# Power_Management_System.net
KiCad netlist of a schematic drawn in Altium Designer
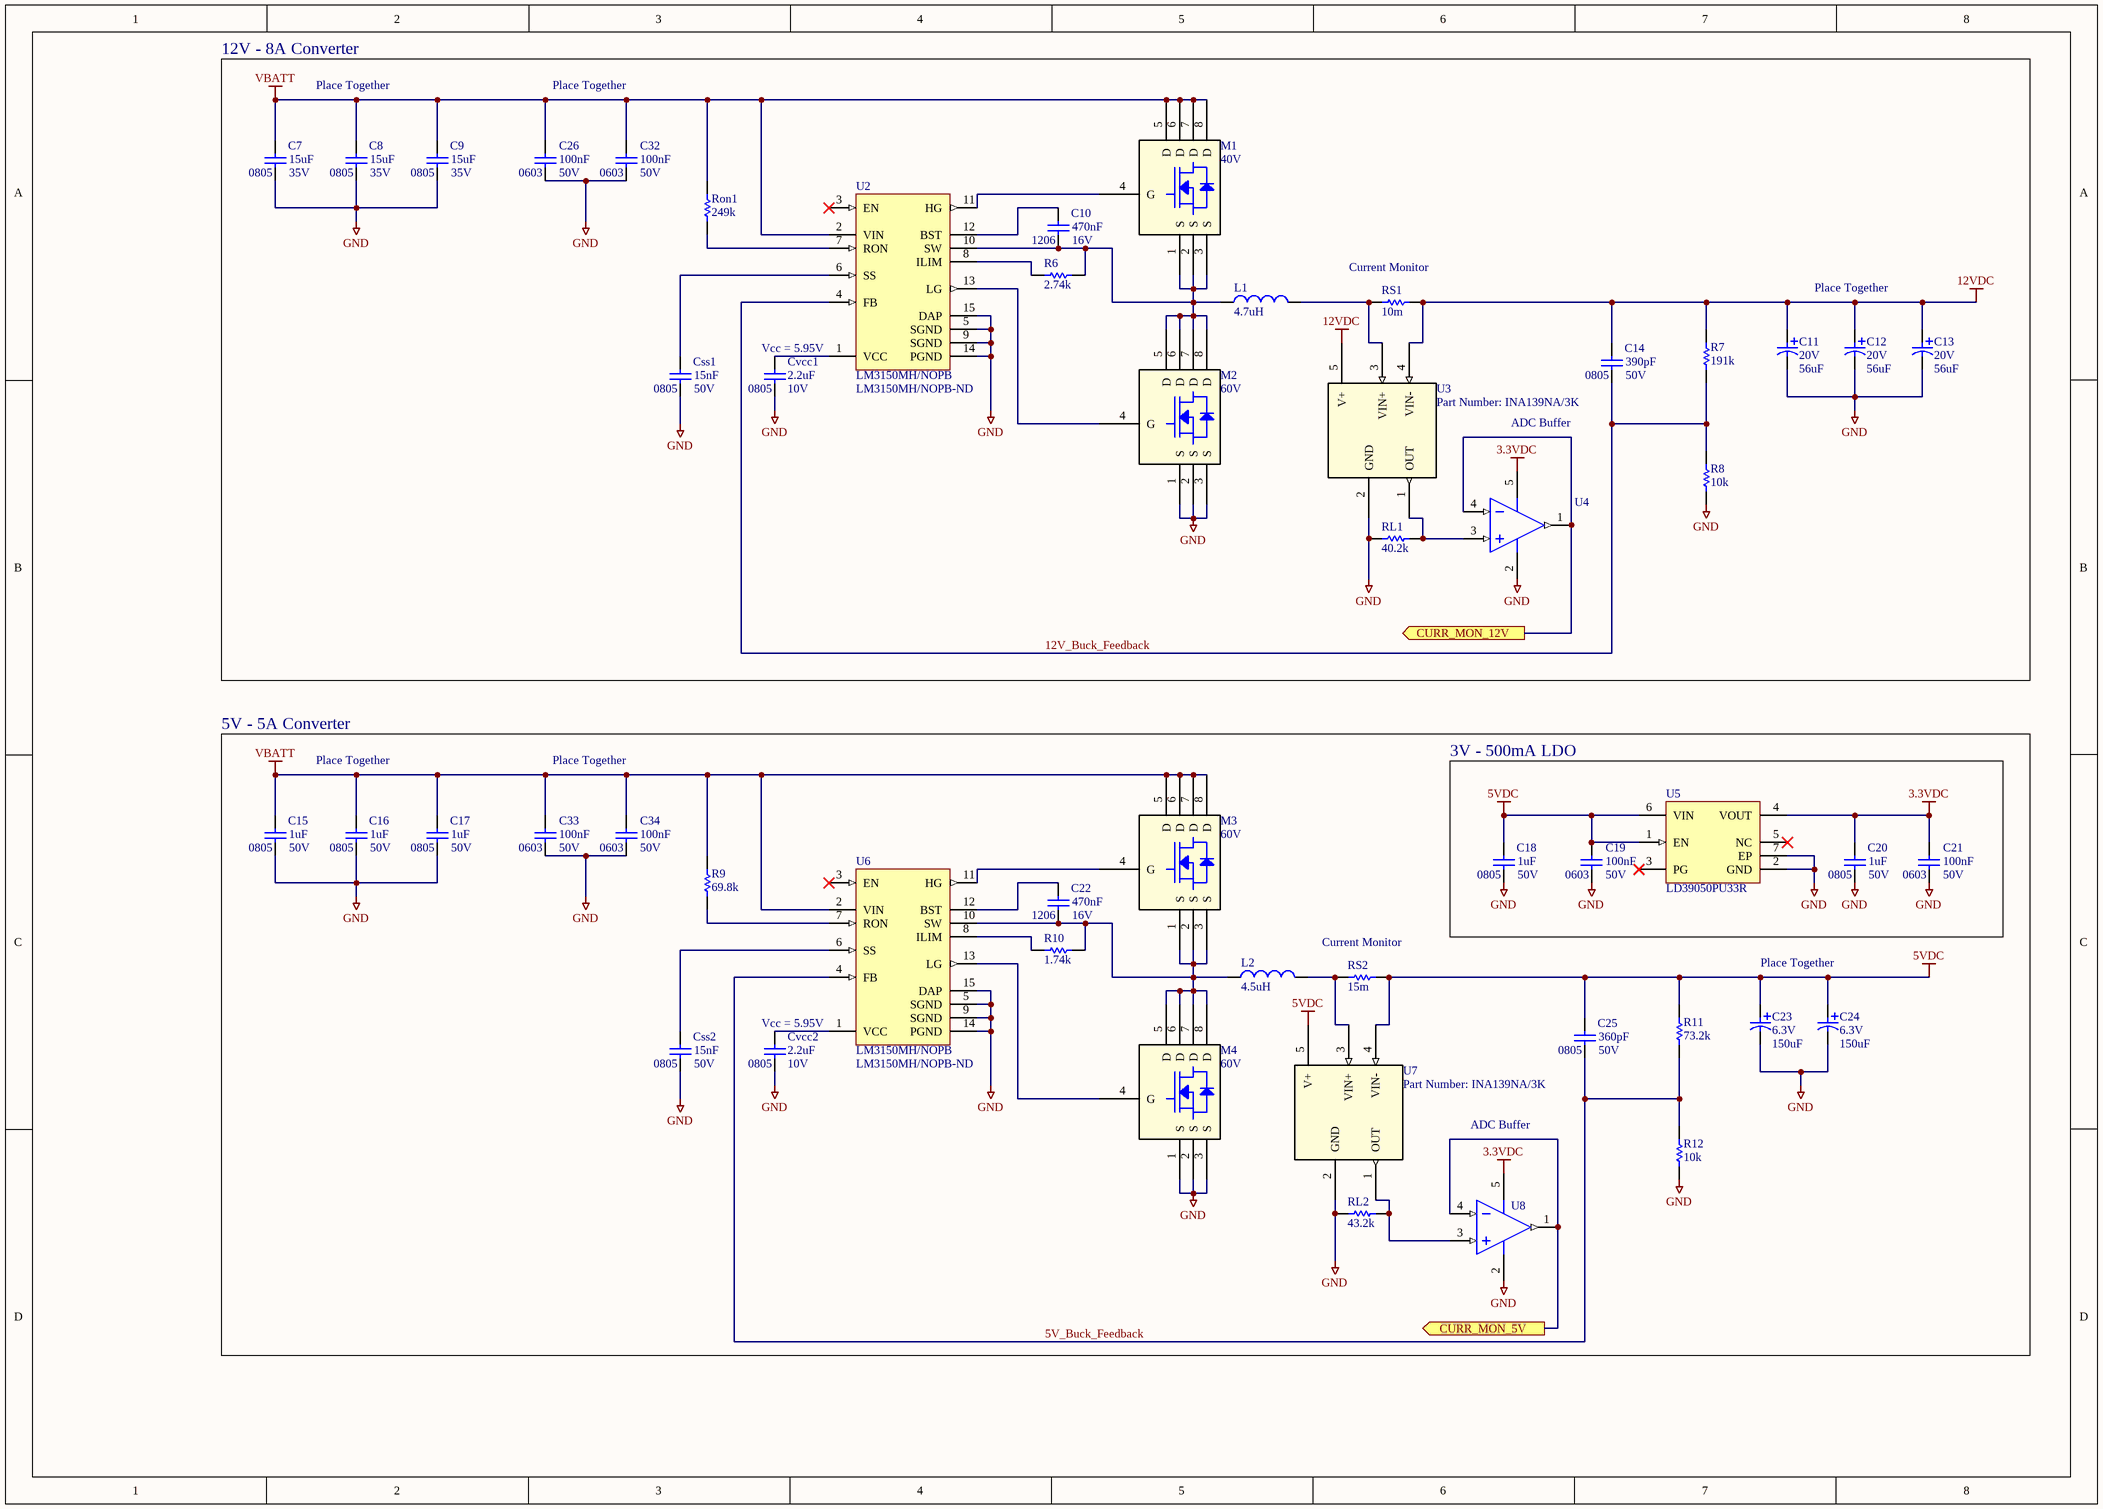
[diagram p0: Power_Management_System.SchDoc]

(export (version "E")
  (design (tool "Eeschema 10.0.6"))
  (components
    (comp (ref "C7")
      (value "C2012X5R1V156M125AC")
      (footprint "CAPC2012N(0805\")")
      (description "CAP CER 15UF 35V X5R 0805")
      (fields
        (field (name "MANUFACTURER") "TDK")
        (field (name "TOLERANCE") "20%")
        (field (name "VOLTAGE RATING") "35V")
        (field (name "CASE/PACKAGE") "0805")
        (field (name "CAPACITANCE") "15uF")
      )
      (libsource (lib "BLDC_Gimbal_Prototype_Lib") (part "C2012X5R1V156M125AC"))
    )
    (comp (ref "C8")
      (value "C2012X5R1V156M125AC")
      (footprint "CAPC2012N(0805\")")
      (description "CAP CER 15UF 35V X5R 0805")
      (fields
        (field (name "MANUFACTURER") "TDK")
        (field (name "TOLERANCE") "20%")
        (field (name "VOLTAGE RATING") "35V")
        (field (name "CASE/PACKAGE") "0805")
        (field (name "CAPACITANCE") "15uF")
      )
      (libsource (lib "BLDC_Gimbal_Prototype_Lib") (part "C2012X5R1V156M125AC"))
    )
    (comp (ref "C9")
      (value "C2012X5R1V156M125AC")
      (footprint "CAPC2012N(0805\")")
      (description "CAP CER 15UF 35V X5R 0805")
      (fields
        (field (name "MANUFACTURER") "TDK")
        (field (name "TOLERANCE") "20%")
        (field (name "VOLTAGE RATING") "35V")
        (field (name "CASE/PACKAGE") "0805")
        (field (name "CAPACITANCE") "15uF")
      )
      (libsource (lib "BLDC_Gimbal_Prototype_Lib") (part "C2012X5R1V156M125AC"))
    )
    (comp (ref "C10")
      (value "ECP-U1C474MA5")
      (footprint "CAPC3216N(1206\")")
      (description "CAP FILM 0.47UF 20% 16VDC 1206")
      (fields
        (field (name "MANUFACTURER") "Panasonic")
        (field (name "TOLERANCE") "20%")
        (field (name "VOLTAGE RATING") "16V")
        (field (name "CASE CODE (IMPERIAL)") "1206")
        (field (name "CAPACITANCE") "470nF")
      )
      (libsource (lib "BLDC_Gimbal_Prototype_Lib") (part "ECP-U1C474MA5"))
    )
    (comp (ref "C11")
      (value "20SVPF56MX")
      (footprint "PCAP_SVP_B6-M")
      (description "CAP ALUM POLY 56UF 20% 20V SMD")
      (fields
        (field (name "MANUFACTURER") "Panasonic")
        (field (name "TOLERANCE") "20%")
        (field (name "VOLTAGE") "20V")
        (field (name "CAPACITANCE") "56uF")
      )
      (libsource (lib "BLDC_Gimbal_Lib") (part "20SVPF56MX"))
    )
    (comp (ref "C12")
      (value "20SVPF56MX")
      (footprint "PCAP_SVP_B6-M")
      (description "CAP ALUM POLY 56UF 20% 20V SMD")
      (fields
        (field (name "MANUFACTURER") "Panasonic")
        (field (name "TOLERANCE") "20%")
        (field (name "VOLTAGE") "20V")
        (field (name "CAPACITANCE") "56uF")
      )
      (libsource (lib "BLDC_Gimbal_Lib") (part "20SVPF56MX"))
    )
    (comp (ref "C13")
      (value "20SVPF56MX")
      (footprint "PCAP_SVP_B6-M")
      (description "CAP ALUM POLY 56UF 20% 20V SMD")
      (fields
        (field (name "MANUFACTURER") "Panasonic")
        (field (name "TOLERANCE") "20%")
        (field (name "VOLTAGE") "20V")
        (field (name "CAPACITANCE") "56uF")
      )
      (libsource (lib "BLDC_Gimbal_Lib") (part "20SVPF56MX"))
    )
    (comp (ref "C14")
      (value "C0805C391J5GACTU")
      (footprint "CAPC2012N(0805\")")
      (description "CAP CER 390PF 50V C0G/NP0 0805")
      (fields
        (field (name "MANUFACTURER") "KEMET")
        (field (name "TOLERANCE") "5%")
        (field (name "VOLTAGE") "50V")
        (field (name "CASE/PACKAGE") "0805")
        (field (name "CAPACITANCE") "390pF")
      )
      (libsource (lib "BLDC_Gimbal_Prototype_Lib") (part "C0805C391J5GACTU"))
    )
    (comp (ref "C15")
      (value "CL21A105KBCLNNC")
      (footprint "CAPC2012N(0805\")")
      (description "CAP CER 1uF 50V X5R 10% SMD 0805 85C Cardboard T/R")
      (fields
        (field (name "MANUFACTURER") "Samsung")
        (field (name "TOLERANCE") "10%")
        (field (name "VOLTAGE RATING") "50V")
        (field (name "CASE/PACKAGE") "0805")
        (field (name "CAPACITANCE") "1uF")
      )
      (libsource (lib "BLDC_Gimbal_Prototype_Lib") (part "CL21A105KBCLNNC"))
    )
    (comp (ref "C16")
      (value "CL21A105KBCLNNC")
      (footprint "CAPC2012N(0805\")")
      (description "CAP CER 1uF 50V X5R 10% SMD 0805 85C Cardboard T/R")
      (fields
        (field (name "MANUFACTURER") "Samsung")
        (field (name "TOLERANCE") "10%")
        (field (name "VOLTAGE RATING") "50V")
        (field (name "CASE/PACKAGE") "0805")
        (field (name "CAPACITANCE") "1uF")
      )
      (libsource (lib "BLDC_Gimbal_Prototype_Lib") (part "CL21A105KBCLNNC"))
    )
    (comp (ref "C17")
      (value "CL21A105KBCLNNC")
      (footprint "CAPC2012N(0805\")")
      (description "CAP CER 1uF 50V X5R 10% SMD 0805 85C Cardboard T/R")
      (fields
        (field (name "MANUFACTURER") "Samsung")
        (field (name "TOLERANCE") "10%")
        (field (name "VOLTAGE RATING") "50V")
        (field (name "CASE/PACKAGE") "0805")
        (field (name "CAPACITANCE") "1uF")
      )
      (libsource (lib "BLDC_Gimbal_Prototype_Lib") (part "CL21A105KBCLNNC"))
    )
    (comp (ref "C18")
      (value "CL21A105KBCLNNC")
      (footprint "CAPC2012N(0805\")")
      (description "CAP CER 1uF 50V X5R 10% SMD 0805 85C Cardboard T/R")
      (fields
        (field (name "MANUFACTURER") "Samsung")
        (field (name "TOLERANCE") "10%")
        (field (name "VOLTAGE RATING") "50V")
        (field (name "CASE/PACKAGE") "0805")
        (field (name "CAPACITANCE") "1uF")
      )
      (libsource (lib "BLDC_Gimbal_Lib") (part "CL21A105KBCLNNC"))
    )
    (comp (ref "C19")
      (value "100nF")
      (footprint "CAPC1608N(0603\")")
      (description "CAP CER 0.1UF 50V X7R 0603")
      (fields
        (field (name "MANUFACTURER") "Samsung")
        (field (name "MANUFACTURER PART NUMBER") "CL10B104KB8SFNC")
        (field (name "CASE CODE (IMPERIAL)") "0603")
        (field (name "VOLTAGE RATING") "50V")
      )
      (libsource (lib "BLDC_Gimbal_Lib") (part "CL10B104KB8SFNC"))
    )
    (comp (ref "C20")
      (value "CL21A105KBCLNNC")
      (footprint "CAPC2012N(0805\")")
      (description "CAP CER 1uF 50V X5R 10% SMD 0805 85C Cardboard T/R")
      (fields
        (field (name "MANUFACTURER") "Samsung")
        (field (name "TOLERANCE") "10%")
        (field (name "VOLTAGE RATING") "50V")
        (field (name "CASE/PACKAGE") "0805")
        (field (name "CAPACITANCE") "1uF")
      )
      (libsource (lib "BLDC_Gimbal_Lib") (part "CL21A105KBCLNNC"))
    )
    (comp (ref "C21")
      (value "100nF")
      (footprint "CAPC1608N(0603\")")
      (description "CAP CER 0.1UF 50V X7R 0603")
      (fields
        (field (name "MANUFACTURER") "Samsung")
        (field (name "MANUFACTURER PART NUMBER") "CL10B104KB8SFNC")
        (field (name "CASE CODE (IMPERIAL)") "0603")
        (field (name "VOLTAGE RATING") "50V")
      )
      (libsource (lib "BLDC_Gimbal_Lib") (part "CL10B104KB8SFNC"))
    )
    (comp (ref "C22")
      (value "ECP-U1C474MA5")
      (footprint "CAPC3216N(1206\")")
      (description "CAP FILM 0.47UF 20% 16VDC 1206")
      (fields
        (field (name "MANUFACTURER") "Panasonic")
        (field (name "TOLERANCE") "20%")
        (field (name "VOLTAGE RATING") "16V")
        (field (name "CASE CODE (IMPERIAL)") "1206")
        (field (name "CAPACITANCE") "470nF")
      )
      (libsource (lib "BLDC_Gimbal_Prototype_Lib") (part "ECP-U1C474MA5"))
    )
    (comp (ref "C23")
      (value "6SVPE150M")
      (footprint "PCAP_SVP_B6-M")
      (description "CAP ALUM POLY 150UF 20% 6.3V SMD")
      (fields
        (field (name "MANUFACTURER") "Panasonic")
        (field (name "TOLERANCE") "20%")
        (field (name "VOLTAGE") "6.3V")
        (field (name "CAPACITANCE") "150uF")
      )
      (libsource (lib "BLDC_Gimbal_Lib") (part "6SVPE150M"))
    )
    (comp (ref "C24")
      (value "6SVPE150M")
      (footprint "PCAP_SVP_B6-M")
      (description "CAP ALUM POLY 150UF 20% 6.3V SMD")
      (fields
        (field (name "MANUFACTURER") "Panasonic")
        (field (name "TOLERANCE") "20%")
        (field (name "VOLTAGE") "6.3V")
        (field (name "CAPACITANCE") "150uF")
      )
      (libsource (lib "BLDC_Gimbal_Lib") (part "6SVPE150M"))
    )
    (comp (ref "C25")
      (value "CL21C361JBANNNC")
      (footprint "CAPC2012N(0805\")")
      (description "CAP CER 360pF 50V C0G 5% SMD 0805 125C Paper T/R")
      (fields
        (field (name "MANUFACTURER") "Samsung")
        (field (name "TOLERANCE") "5%")
        (field (name "VOLTAGE RATING") "50V")
        (field (name "CASE/PACKAGE") "0805")
        (field (name "CAPACITANCE") "360pF")
      )
      (libsource (lib "BLDC_Gimbal_Prototype_Lib") (part "CL21C361JBANNNC"))
    )
    (comp (ref "C26")
      (value "100nF")
      (footprint "CAPC1608N(0603\")")
      (description "CAP CER 0.1UF 50V X7R 0603")
      (fields
        (field (name "MANUFACTURER") "Samsung")
        (field (name "MANUFACTURER PART NUMBER") "CL10B104KB8SFNC")
        (field (name "CASE CODE (IMPERIAL)") "0603")
        (field (name "VOLTAGE RATING") "50V")
      )
      (libsource (lib "BLDC_Gimbal_Lib") (part "CL10B104KB8SFNC"))
    )
    (comp (ref "C32")
      (value "100nF")
      (footprint "CAPC1608N(0603\")")
      (description "CAP CER 0.1UF 50V X7R 0603")
      (fields
        (field (name "MANUFACTURER") "Samsung")
        (field (name "MANUFACTURER PART NUMBER") "CL10B104KB8SFNC")
        (field (name "CASE CODE (IMPERIAL)") "0603")
        (field (name "VOLTAGE RATING") "50V")
      )
      (libsource (lib "BLDC_Gimbal_Lib") (part "CL10B104KB8SFNC"))
    )
    (comp (ref "C33")
      (value "100nF")
      (footprint "CAPC1608N(0603\")")
      (description "CAP CER 0.1UF 50V X7R 0603")
      (fields
        (field (name "MANUFACTURER") "Samsung")
        (field (name "MANUFACTURER PART NUMBER") "CL10B104KB8SFNC")
        (field (name "CASE CODE (IMPERIAL)") "0603")
        (field (name "VOLTAGE RATING") "50V")
      )
      (libsource (lib "BLDC_Gimbal_Lib") (part "CL10B104KB8SFNC"))
    )
    (comp (ref "C34")
      (value "100nF")
      (footprint "CAPC1608N(0603\")")
      (description "CAP CER 0.1UF 50V X7R 0603")
      (fields
        (field (name "MANUFACTURER") "Samsung")
        (field (name "MANUFACTURER PART NUMBER") "CL10B104KB8SFNC")
        (field (name "CASE CODE (IMPERIAL)") "0603")
        (field (name "VOLTAGE RATING") "50V")
      )
      (libsource (lib "BLDC_Gimbal_Lib") (part "CL10B104KB8SFNC"))
    )
    (comp (ref "Css1")
      (value "CGA4F2C0G1H153J085AA")
      (footprint "CAPC2012N(0805\")")
      (description "CAP, 0.015µF, 50V, 5%, C0G/NP0, 0805")
      (fields
        (field (name "MANUFACTURER") "TDK")
        (field (name "TOLERANCE") "5%")
        (field (name "VOLTAGE RATING") "50V")
        (field (name "CASE/PACKAGE") "0805")
        (field (name "CAPACITANCE") "15nF")
      )
      (libsource (lib "BLDC_Gimbal_Prototype_Lib") (part "CGA4F2C0G1H153J085AA"))
    )
    (comp (ref "Css2")
      (value "CGA4F2C0G1H153J085AA")
      (footprint "CAPC2012N(0805\")")
      (description "CAP, 0.015µF, 50V, 5%, C0G/NP0, 0805")
      (fields
        (field (name "MANUFACTURER") "TDK")
        (field (name "TOLERANCE") "5%")
        (field (name "VOLTAGE RATING") "50V")
        (field (name "CASE/PACKAGE") "0805")
        (field (name "CAPACITANCE") "15nF")
      )
      (libsource (lib "BLDC_Gimbal_Prototype_Lib") (part "CGA4F2C0G1H153J085AA"))
    )
    (comp (ref "Cvcc1")
      (value "LMK212B7225KG-T")
      (footprint "CAPC2012N(0805\")")
      (description "CAP CER 2.2UF 10V X7R 0805")
      (fields
        (field (name "MANUFACTURER") "Taiyo Yuden")
        (field (name "TOLERANCE") "10%")
        (field (name "CAPACITANCE") "2.2uF")
        (field (name "VOLTAGE RATING") "10V")
        (field (name "CASE/PACKAGE") "0805")
      )
      (libsource (lib "BLDC_Gimbal_Prototype_Lib") (part "LMK212B7225KG-T"))
    )
    (comp (ref "Cvcc2")
      (value "LMK212B7225KG-T")
      (footprint "CAPC2012N(0805\")")
      (description "CAP CER 2.2UF 10V X7R 0805")
      (fields
        (field (name "MANUFACTURER") "Taiyo Yuden")
        (field (name "TOLERANCE") "10%")
        (field (name "CAPACITANCE") "2.2uF")
        (field (name "VOLTAGE RATING") "10V")
        (field (name "CASE/PACKAGE") "0805")
      )
      (libsource (lib "BLDC_Gimbal_Prototype_Lib") (part "LMK212B7225KG-T"))
    )
    (comp (ref "L1")
      (value "SRP1270-4R7M")
      (footprint "IND_BOURNS_SRP01_large")
      (description "FIXED IND 4.7uH 20% SMD 1270")
      (fields
        (field (name "MANUFACTURER") "Bourns")
        (field (name "TOLERANCE") "20%")
        (field (name "INDUCTANCE") "4.7uH")
      )
      (libsource (lib "BLDC_Gimbal_Lib") (part "SRP1270-4R7M"))
    )
    (comp (ref "L2")
      (value "SRR1208-4R5ML")
      (footprint "IND_BOURNS_SRR12")
      (description "FIXED IND 4.5UH 6.5A 14 MOHM SMD")
      (fields
        (field (name "MANUFACTURER") "Bourns")
        (field (name "TOLERANCE") "20%")
        (field (name "INDUCTANCE") "4.5uH")
      )
      (libsource (lib "BLDC_Gimbal_Lib") (part "SRR1208-4R5ML"))
    )
    (comp (ref "M1")
      (value "CSD18504Q5A")
      (footprint "DQJ8")
      (description "MOSFET N-CH 40V 8SON")
      (fields
        (field (name "MANUFACTURER") "Texas Instruments")
        (field (name "DRAIN TO SOURCE VOLTAGE (VDSS)") "40V")
      )
      (libsource (lib "BLDC_Gimbal_Prototype_Lib") (part "CSD18504Q5A"))
    )
    (comp (ref "M2")
      (value "CSD18537NQ5A")
      (footprint "DQJ8")
      (description "MOSFET N-CH 60V 50A 8-Pin VSON-FET EP T/R")
      (fields
        (field (name "MANUFACTURER") "Texas Instruments")
        (field (name "DRAIN TO SOURCE VOLTAGE (VDSS)") "60V")
      )
      (libsource (lib "BLDC_Gimbal_Prototype_Lib") (part "CSD18537NQ5A"))
    )
    (comp (ref "M3")
      (value "CSD18537NQ5A")
      (footprint "DQJ8")
      (description "MOSFET N-CH 60V 50A 8-Pin VSON-FET EP T/R")
      (fields
        (field (name "MANUFACTURER") "Texas Instruments")
        (field (name "DRAIN TO SOURCE VOLTAGE (VDSS)") "60V")
      )
      (libsource (lib "BLDC_Gimbal_Prototype_Lib") (part "CSD18537NQ5A"))
    )
    (comp (ref "M4")
      (value "CSD18537NQ5A")
      (footprint "DQJ8")
      (description "MOSFET N-CH 60V 50A 8-Pin VSON-FET EP T/R")
      (fields
        (field (name "MANUFACTURER") "Texas Instruments")
        (field (name "DRAIN TO SOURCE VOLTAGE (VDSS)") "60V")
      )
      (libsource (lib "BLDC_Gimbal_Prototype_Lib") (part "CSD18537NQ5A"))
    )
    (comp (ref "R6")
      (value "ERJ-6ENF2741V")
      (footprint "RESC2012N(0805\")")
      (description "RES SMD 2.74K OHM 1% 1/8W 0805")
      (fields
        (field (name "MANUFACTURER") "Panasonic")
        (field (name "TOLERANCE") "1%")
        (field (name "RESISTANCE") "2.74k")
      )
      (libsource (lib "BLDC_Gimbal_Prototype_Lib") (part "ERJ-6ENF2741V"))
    )
    (comp (ref "R7")
      (value "ERJ-6ENF1913V")
      (footprint "RESC2012N(0805\")")
      (description "RES SMD 191K OHM 1% 1/8W 0805")
      (fields
        (field (name "MANUFACTURER") "Panasonic")
        (field (name "TOLERANCE") "1%")
        (field (name "RESISTANCE") "191k")
      )
      (libsource (lib "BLDC_Gimbal_Prototype_Lib") (part "ERJ-6ENF1913V"))
    )
    (comp (ref "R8")
      (value "CRCW080510K0FKEA")
      (footprint "RESC2012N(0805\")")
      (description "RES SMD 10K OHM 1% 1/8W 0805")
      (fields
        (field (name "MANUFACTURER") "Vishay")
        (field (name "TOLERANCE") "1%")
        (field (name "RESISTANCE") "10k")
      )
      (libsource (lib "BLDC_Gimbal_Prototype_Lib") (part "CRCW080510K0FKEA"))
    )
    (comp (ref "R9")
      (value "ERJ-6ENF6982V")
      (footprint "RESC2012N(0805\")")
      (description "RES SMD 69.8K OHM 1% 1/8W 0805")
      (fields
        (field (name "MANUFACTURER") "Panasonic")
        (field (name "TOLERANCE") "1%")
        (field (name "RESISTANCE") "69.8k")
      )
      (libsource (lib "BLDC_Gimbal_Prototype_Lib") (part "ERJ-6ENF6982V"))
    )
    (comp (ref "R10")
      (value "ERJ6ENF1741V")
      (footprint "RESC2012N(0805\")")
      (description "RES SMD 1.74K OHM 1% 1/8W 0805")
      (fields
        (field (name "MANUFACTURER") "Panasonic")
        (field (name "TOLERANCE") "1%")
        (field (name "RESISTANCE") "1.74k")
      )
      (libsource (lib "BLDC_Gimbal_Prototype_Lib") (part "ERJ6ENF1741V"))
    )
    (comp (ref "R11")
      (value "ERJ-6ENF7322V")
      (footprint "RESC2012N(0805\")")
      (description "RES SMD 73.2K OHM 1% 1/8W 0805")
      (fields
        (field (name "MANUFACTURER") "Panasonic")
        (field (name "TOLERANCE") "1%")
        (field (name "RESISTANCE") "73.2k")
      )
      (libsource (lib "BLDC_Gimbal_Prototype_Lib") (part "ERJ-6ENF7322V"))
    )
    (comp (ref "R12")
      (value "CRCW080510K0FKEA")
      (footprint "RESC2012N(0805\")")
      (description "RES SMD 10K OHM 1% 1/8W 0805")
      (fields
        (field (name "MANUFACTURER") "Vishay")
        (field (name "TOLERANCE") "1%")
        (field (name "RESISTANCE") "10k")
      )
      (libsource (lib "BLDC_Gimbal_Prototype_Lib") (part "CRCW080510K0FKEA"))
    )
    (comp (ref "RL1")
      (value "ERA3AEB4022V")
      (footprint "RESC1608N(0603\")")
      (description "RES SMD 40.2K OHM 0.1% 1/10W 0603")
      (fields
        (field (name "MANUFACTURER") "Panasonic")
        (field (name "TOLERANCE") "0.1%")
        (field (name "RESISTANCE") "40.2k")
      )
      (libsource (lib "BLDC_Gimbal_Prototype_Lib") (part "ERA3AEB4022V"))
    )
    (comp (ref "RL2")
      (value "ERA3AEB4322V")
      (footprint "RESC1608N(0603\")")
      (description "RES SMD 43.2K OHM 0.1% 1/10W 0603")
      (fields
        (field (name "MANUFACTURER") "Panasonic")
        (field (name "TOLERANCE") "0.1%")
        (field (name "RESISTANCE") "43.2k")
      )
      (libsource (lib "BLDC_Gimbal_Prototype_Lib") (part "ERA3AEB4322V"))
    )
    (comp (ref "Ron1")
      (value "CRCW0805249KFKEA")
      (footprint "RESC2012N(0805\")")
      (description "RES SMD 249K OHM 1% 1/8W 0805")
      (fields
        (field (name "MANUFACTURER") "Vishay")
        (field (name "TOLERANCE") "1%")
        (field (name "RESISTANCE") "249k")
      )
      (libsource (lib "BLDC_Gimbal_Prototype_Lib") (part "CRCW0805249KFKEA"))
    )
    (comp (ref "RS1")
      (value "CRA2512-FZ-R010ELF")
      (footprint "RESC6332N(2512\")")
      (description "RES SMD 10 MOHM, 2512 [6432 Metric], 3 W,  1%, CR Series")
      (fields
        (field (name "MANUFACTURER") "Bourns")
        (field (name "TOLERANCE") "1%")
        (field (name "RESISTANCE") "10m")
      )
      (libsource (lib "BLDC_Gimbal_Prototype_Lib") (part "CRA2512-FZ-R010ELF"))
    )
    (comp (ref "RS2")
      (value "CRA2512-FZ-R015ELF")
      (footprint "RESC6332N(2512\")")
      (description "RES SMD 15 MOHM 1% 3W 2512")
      (fields
        (field (name "MANUFACTURER") "Bourns")
        (field (name "TOLERANCE") "1%")
        (field (name "RESISTANCE") "15m")
      )
      (libsource (lib "BLDC_Gimbal_Prototype_Lib") (part "CRA2512-FZ-R015ELF"))
    )
    (comp (ref "U2")
      (value "LM3150MH/NOPB")
      (footprint "PWP0014A_M")
      (description "LM3150 - DC DC Cntrlr Single-OUT Step Down 6V to 42V Input 14-Pin HTSSOP EP Tube")
      (fields
        (field (name "MANUFACTURER") "TI National Semiconductor")
        (field (name "SUPPLIER PART NUMBER 1") "LM3150MH/NOPB-ND")
      )
      (libsource (lib "BLDC_Gimbal_Lib") (part "LM3150MH/NOPB"))
    )
    (comp (ref "U3")
      (value "Part Number: INA139NA/3K")
      (footprint "DBV5-M")
      (description "No Description Available")
      (fields
        (field (name "MANUFACTURER") "Texas Instruments")
        (field (name "MANUFACTURER_PART_NUMBER") "INA139NA/3K")
        (field (name "COPYRIGHT") "Copyright (C) 2018 Accelerated Designs. All rights reserved")
      )
      (libsource (lib "BLDC_Gimbal_Prototype_Lib") (part "INA139NA/3K"))
    )
    (comp (ref "U4")
      (value "OPA340NA/3K")
      (footprint "DBV0005A_M")
      (fields (field (name "MANUFACTURER") "Texas Instruments"))
      (libsource (lib "BLDC_Gimbal_Prototype_Lib") (part "CMP-0272-00929-3"))
    )
    (comp (ref "U5")
      (value "LD39050PU33R")
      (footprint "LDO3_3-DFN6D_M")
      (libsource (lib "BLDC_Gimbal_Lib") (part "LD39050PU33R"))
    )
    (comp (ref "U6")
      (value "LM3150MH/NOPB")
      (footprint "PWP0014A_M")
      (description "LM3150 - DC DC Cntrlr Single-OUT Step Down 6V to 42V Input 14-Pin HTSSOP EP Tube")
      (fields
        (field (name "MANUFACTURER") "TI National Semiconductor")
        (field (name "SUPPLIER PART NUMBER 1") "LM3150MH/NOPB-ND")
      )
      (libsource (lib "BLDC_Gimbal_Lib") (part "LM3150MH/NOPB"))
    )
    (comp (ref "U7")
      (value "Part Number: INA139NA/3K")
      (footprint "DBV5-M")
      (description "No Description Available")
      (fields
        (field (name "MANUFACTURER") "Texas Instruments")
        (field (name "MANUFACTURER_PART_NUMBER") "INA139NA/3K")
        (field (name "COPYRIGHT") "Copyright (C) 2018 Accelerated Designs. All rights reserved")
      )
      (libsource (lib "BLDC_Gimbal_Prototype_Lib") (part "INA139NA/3K"))
    )
    (comp (ref "U8")
      (value "OPA340NA/3K")
      (footprint "DBV0005A_M")
      (fields (field (name "MANUFACTURER") "Texas Instruments"))
      (libsource (lib "BLDC_Gimbal_Prototype_Lib") (part "CMP-0272-00929-3"))
    )
  )
  (nets
    (net (code "1") (name "/5V_Buck_Feedback") (class "Default")
      (node (ref "C25") (pin "1") (pinfunction "1_1") (pintype "passive"))
      (node (ref "R11") (pin "1") (pinfunction "1_1") (pintype "passive"))
      (node (ref "R12") (pin "2") (pinfunction "2_2") (pintype "passive"))
      (node (ref "U6") (pin "4") (pinfunction "FB_4") (pintype "input"))
    )
    (net (code "2") (name "/12V_Buck_Feedback") (class "Default")
      (node (ref "C14") (pin "1") (pinfunction "1_1") (pintype "passive"))
      (node (ref "R7") (pin "1") (pinfunction "1_1") (pintype "passive"))
      (node (ref "R8") (pin "2") (pinfunction "2_2") (pintype "passive"))
      (node (ref "U2") (pin "4") (pinfunction "FB_4") (pintype "input"))
    )
    (net (code "3") (name "/CURR_MON_5V") (class "Default")
      (node (ref "U8") (pin "1") (pinfunction "OUT_1") (pintype "output"))
      (node (ref "U8") (pin "4") (pinfunction "IN-_4") (pintype "input"))
    )
    (net (code "4") (name "/CURR_MON_12V") (class "Default")
      (node (ref "U4") (pin "1") (pinfunction "OUT_1") (pintype "output"))
      (node (ref "U4") (pin "4") (pinfunction "IN-_4") (pintype "input"))
    )
    (net (code "5") (name "3.3VDC") (class "Default")
      (node (ref "C20") (pin "2") (pinfunction "2_2") (pintype "passive"))
      (node (ref "C21") (pin "2") (pinfunction "2_2") (pintype "passive"))
      (node (ref "U4") (pin "5") (pinfunction "V+_5") (pintype "power_in"))
      (node (ref "U5") (pin "4") (pinfunction "VOUT_4") (pintype "power_in"))
      (node (ref "U8") (pin "5") (pinfunction "V+_5") (pintype "power_in"))
    )
    (net (code "6") (name "5VDC") (class "Default")
      (node (ref "C18") (pin "2") (pinfunction "2_2") (pintype "passive"))
      (node (ref "C19") (pin "2") (pinfunction "2_2") (pintype "passive"))
      (node (ref "C23") (pin "1") (pinfunction "1_1") (pintype "passive"))
      (node (ref "C24") (pin "1") (pinfunction "1_1") (pintype "passive"))
      (node (ref "C25") (pin "2") (pinfunction "2_2") (pintype "passive"))
      (node (ref "R11") (pin "2") (pinfunction "2_2") (pintype "passive"))
      (node (ref "RS2") (pin "2") (pinfunction "2_2") (pintype "passive"))
      (node (ref "U5") (pin "1") (pinfunction "EN_1") (pintype "input"))
      (node (ref "U5") (pin "6") (pinfunction "VIN_6") (pintype "power_in"))
      (node (ref "U7") (pin "4") (pinfunction "VIN-_4") (pintype "input"))
      (node (ref "U7") (pin "5") (pinfunction "V+_5") (pintype "power_in"))
    )
    (net (code "7") (name "12VDC") (class "Default")
      (node (ref "C11") (pin "1") (pinfunction "1_1") (pintype "passive"))
      (node (ref "C12") (pin "1") (pinfunction "1_1") (pintype "passive"))
      (node (ref "C13") (pin "1") (pinfunction "1_1") (pintype "passive"))
      (node (ref "C14") (pin "2") (pinfunction "2_2") (pintype "passive"))
      (node (ref "R7") (pin "2") (pinfunction "2_2") (pintype "passive"))
      (node (ref "RS1") (pin "2") (pinfunction "2_2") (pintype "passive"))
      (node (ref "U3") (pin "4") (pinfunction "VIN-_4") (pintype "input"))
      (node (ref "U3") (pin "5") (pinfunction "V+_5") (pintype "power_in"))
    )
    (net (code "8") (name "GND") (class "Default")
      (node (ref "C11") (pin "2") (pinfunction "2_2") (pintype "passive"))
      (node (ref "C12") (pin "2") (pinfunction "2_2") (pintype "passive"))
      (node (ref "C13") (pin "2") (pinfunction "2_2") (pintype "passive"))
      (node (ref "C15") (pin "1") (pinfunction "1_1") (pintype "passive"))
      (node (ref "C16") (pin "1") (pinfunction "1_1") (pintype "passive"))
      (node (ref "C17") (pin "1") (pinfunction "1_1") (pintype "passive"))
      (node (ref "C18") (pin "1") (pinfunction "1_1") (pintype "passive"))
      (node (ref "C19") (pin "1") (pinfunction "1_1") (pintype "passive"))
      (node (ref "C20") (pin "1") (pinfunction "1_1") (pintype "passive"))
      (node (ref "C21") (pin "1") (pinfunction "1_1") (pintype "passive"))
      (node (ref "C23") (pin "2") (pinfunction "2_2") (pintype "passive"))
      (node (ref "C24") (pin "2") (pinfunction "2_2") (pintype "passive"))
      (node (ref "C26") (pin "1") (pinfunction "1_1") (pintype "passive"))
      (node (ref "C32") (pin "1") (pinfunction "1_1") (pintype "passive"))
      (node (ref "C33") (pin "1") (pinfunction "1_1") (pintype "passive"))
      (node (ref "C34") (pin "1") (pinfunction "1_1") (pintype "passive"))
      (node (ref "C7") (pin "1") (pinfunction "1_1") (pintype "passive"))
      (node (ref "C8") (pin "1") (pinfunction "1_1") (pintype "passive"))
      (node (ref "C9") (pin "1") (pinfunction "1_1") (pintype "passive"))
      (node (ref "Css1") (pin "1") (pinfunction "1_1") (pintype "passive"))
      (node (ref "Css2") (pin "1") (pinfunction "1_1") (pintype "passive"))
      (node (ref "Cvcc1") (pin "1") (pinfunction "1_1") (pintype "passive"))
      (node (ref "Cvcc2") (pin "1") (pinfunction "1_1") (pintype "passive"))
      (node (ref "M2") (pin "1") (pinfunction "S_1") (pintype "passive"))
      (node (ref "M2") (pin "2") (pinfunction "S_2") (pintype "passive"))
      (node (ref "M2") (pin "3") (pinfunction "S_3") (pintype "passive"))
      (node (ref "M4") (pin "1") (pinfunction "S_1") (pintype "passive"))
      (node (ref "M4") (pin "2") (pinfunction "S_2") (pintype "passive"))
      (node (ref "M4") (pin "3") (pinfunction "S_3") (pintype "passive"))
      (node (ref "R12") (pin "1") (pinfunction "1_1") (pintype "passive"))
      (node (ref "R8") (pin "1") (pinfunction "1_1") (pintype "passive"))
      (node (ref "RL1") (pin "1") (pinfunction "1_1") (pintype "passive"))
      (node (ref "RL2") (pin "1") (pinfunction "1_1") (pintype "passive"))
      (node (ref "U2") (pin "14") (pinfunction "PGND_14") (pintype "power_in"))
      (node (ref "U2") (pin "15") (pinfunction "DAP_15") (pintype "power_in"))
      (node (ref "U2") (pin "5") (pinfunction "SGND_5") (pintype "power_in"))
      (node (ref "U2") (pin "9") (pinfunction "SGND_9") (pintype "power_in"))
      (node (ref "U3") (pin "2") (pinfunction "GND_2") (pintype "power_in"))
      (node (ref "U4") (pin "2") (pinfunction "V-_2") (pintype "power_in"))
      (node (ref "U5") (pin "2") (pinfunction "GND_2") (pintype "power_in"))
      (node (ref "U5") (pin "7") (pinfunction "EP_7") (pintype "power_in"))
      (node (ref "U6") (pin "14") (pinfunction "PGND_14") (pintype "power_in"))
      (node (ref "U6") (pin "15") (pinfunction "DAP_15") (pintype "power_in"))
      (node (ref "U6") (pin "5") (pinfunction "SGND_5") (pintype "power_in"))
      (node (ref "U6") (pin "9") (pinfunction "SGND_9") (pintype "power_in"))
      (node (ref "U7") (pin "2") (pinfunction "GND_2") (pintype "power_in"))
      (node (ref "U8") (pin "2") (pinfunction "V-_2") (pintype "power_in"))
    )
    (net (code "9") (name "Net-(M1-G)") (class "Default")
      (node (ref "M1") (pin "4") (pinfunction "G_4") (pintype "passive"))
      (node (ref "U2") (pin "11") (pinfunction "HG_11") (pintype "output"))
    )
    (net (code "10") (name "Net-(M2-G)") (class "Default")
      (node (ref "M2") (pin "4") (pinfunction "G_4") (pintype "passive"))
      (node (ref "U2") (pin "13") (pinfunction "LG_13") (pintype "output"))
    )
    (net (code "11") (name "Net-(M3-G)") (class "Default")
      (node (ref "M3") (pin "4") (pinfunction "G_4") (pintype "passive"))
      (node (ref "U6") (pin "11") (pinfunction "HG_11") (pintype "output"))
    )
    (net (code "12") (name "Net-(M4-G)") (class "Default")
      (node (ref "M4") (pin "4") (pinfunction "G_4") (pintype "passive"))
      (node (ref "U6") (pin "13") (pinfunction "LG_13") (pintype "output"))
    )
    (net (code "13") (name "Net-(U2-BST)") (class "Default")
      (node (ref "C10") (pin "2") (pinfunction "2_2") (pintype "passive"))
      (node (ref "U2") (pin "12") (pinfunction "BST_12") (pintype "passive"))
    )
    (net (code "14") (name "Net-(U2-ILIM)") (class "Default")
      (node (ref "R6") (pin "1") (pinfunction "1_1") (pintype "passive"))
      (node (ref "U2") (pin "8") (pinfunction "ILIM_8") (pintype "passive"))
    )
    (net (code "15") (name "Net-(U2-RON)") (class "Default")
      (node (ref "Ron1") (pin "1") (pinfunction "1_1") (pintype "passive"))
      (node (ref "U2") (pin "7") (pinfunction "RON_7") (pintype "input"))
    )
    (net (code "16") (name "Net-(U2-SS)") (class "Default")
      (node (ref "Css1") (pin "2") (pinfunction "2_2") (pintype "passive"))
      (node (ref "U2") (pin "6") (pinfunction "SS_6") (pintype "input"))
    )
    (net (code "17") (name "Net-(U2-SW)") (class "Default")
      (node (ref "C10") (pin "1") (pinfunction "1_1") (pintype "passive"))
      (node (ref "L1") (pin "1") (pinfunction "1_1") (pintype "passive"))
      (node (ref "M1") (pin "1") (pinfunction "S_1") (pintype "passive"))
      (node (ref "M1") (pin "2") (pinfunction "S_2") (pintype "passive"))
      (node (ref "M1") (pin "3") (pinfunction "S_3") (pintype "passive"))
      (node (ref "M2") (pin "5") (pinfunction "D_5") (pintype "passive"))
      (node (ref "M2") (pin "6") (pinfunction "D_6") (pintype "passive"))
      (node (ref "M2") (pin "7") (pinfunction "D_7") (pintype "passive"))
      (node (ref "M2") (pin "8") (pinfunction "D_8") (pintype "passive"))
      (node (ref "R6") (pin "2") (pinfunction "2_2") (pintype "passive"))
      (node (ref "U2") (pin "10") (pinfunction "SW_10") (pintype "power_in"))
    )
    (net (code "18") (name "Net-(U2-VCC)") (class "Default")
      (node (ref "Cvcc1") (pin "2") (pinfunction "2_2") (pintype "passive"))
      (node (ref "U2") (pin "1") (pinfunction "VCC_1") (pintype "power_in"))
    )
    (net (code "19") (name "Net-(U3-OUT)") (class "Default")
      (node (ref "RL1") (pin "2") (pinfunction "2_2") (pintype "passive"))
      (node (ref "U3") (pin "1") (pinfunction "OUT_1") (pintype "output"))
      (node (ref "U4") (pin "3") (pinfunction "IN+_3") (pintype "input"))
    )
    (net (code "20") (name "Net-(U3-VIN+)") (class "Default")
      (node (ref "L1") (pin "2") (pinfunction "2_2") (pintype "passive"))
      (node (ref "RS1") (pin "1") (pinfunction "1_1") (pintype "passive"))
      (node (ref "U3") (pin "3") (pinfunction "VIN+_3") (pintype "input"))
    )
    (net (code "21") (name "Net-(U6-BST)") (class "Default")
      (node (ref "C22") (pin "2") (pinfunction "2_2") (pintype "passive"))
      (node (ref "U6") (pin "12") (pinfunction "BST_12") (pintype "passive"))
    )
    (net (code "22") (name "Net-(U6-ILIM)") (class "Default")
      (node (ref "R10") (pin "1") (pinfunction "1_1") (pintype "passive"))
      (node (ref "U6") (pin "8") (pinfunction "ILIM_8") (pintype "passive"))
    )
    (net (code "23") (name "Net-(U6-RON)") (class "Default")
      (node (ref "R9") (pin "1") (pinfunction "1_1") (pintype "passive"))
      (node (ref "U6") (pin "7") (pinfunction "RON_7") (pintype "input"))
    )
    (net (code "24") (name "Net-(U6-SS)") (class "Default")
      (node (ref "Css2") (pin "2") (pinfunction "2_2") (pintype "passive"))
      (node (ref "U6") (pin "6") (pinfunction "SS_6") (pintype "input"))
    )
    (net (code "25") (name "Net-(U6-SW)") (class "Default")
      (node (ref "C22") (pin "1") (pinfunction "1_1") (pintype "passive"))
      (node (ref "L2") (pin "1") (pinfunction "1_1") (pintype "passive"))
      (node (ref "M3") (pin "1") (pinfunction "S_1") (pintype "passive"))
      (node (ref "M3") (pin "2") (pinfunction "S_2") (pintype "passive"))
      (node (ref "M3") (pin "3") (pinfunction "S_3") (pintype "passive"))
      (node (ref "M4") (pin "5") (pinfunction "D_5") (pintype "passive"))
      (node (ref "M4") (pin "6") (pinfunction "D_6") (pintype "passive"))
      (node (ref "M4") (pin "7") (pinfunction "D_7") (pintype "passive"))
      (node (ref "M4") (pin "8") (pinfunction "D_8") (pintype "passive"))
      (node (ref "R10") (pin "2") (pinfunction "2_2") (pintype "passive"))
      (node (ref "U6") (pin "10") (pinfunction "SW_10") (pintype "power_in"))
    )
    (net (code "26") (name "Net-(U6-VCC)") (class "Default")
      (node (ref "Cvcc2") (pin "2") (pinfunction "2_2") (pintype "passive"))
      (node (ref "U6") (pin "1") (pinfunction "VCC_1") (pintype "power_in"))
    )
    (net (code "27") (name "Net-(U7-OUT)") (class "Default")
      (node (ref "RL2") (pin "2") (pinfunction "2_2") (pintype "passive"))
      (node (ref "U7") (pin "1") (pinfunction "OUT_1") (pintype "output"))
      (node (ref "U8") (pin "3") (pinfunction "IN+_3") (pintype "input"))
    )
    (net (code "28") (name "Net-(U7-VIN+)") (class "Default")
      (node (ref "L2") (pin "2") (pinfunction "2_2") (pintype "passive"))
      (node (ref "RS2") (pin "1") (pinfunction "1_1") (pintype "passive"))
      (node (ref "U7") (pin "3") (pinfunction "VIN+_3") (pintype "input"))
    )
    (net (code "29") (name "VBATT") (class "Default")
      (node (ref "C15") (pin "2") (pinfunction "2_2") (pintype "passive"))
      (node (ref "C16") (pin "2") (pinfunction "2_2") (pintype "passive"))
      (node (ref "C17") (pin "2") (pinfunction "2_2") (pintype "passive"))
      (node (ref "C26") (pin "2") (pinfunction "2_2") (pintype "passive"))
      (node (ref "C32") (pin "2") (pinfunction "2_2") (pintype "passive"))
      (node (ref "C33") (pin "2") (pinfunction "2_2") (pintype "passive"))
      (node (ref "C34") (pin "2") (pinfunction "2_2") (pintype "passive"))
      (node (ref "C7") (pin "2") (pinfunction "2_2") (pintype "passive"))
      (node (ref "C8") (pin "2") (pinfunction "2_2") (pintype "passive"))
      (node (ref "C9") (pin "2") (pinfunction "2_2") (pintype "passive"))
      (node (ref "M1") (pin "5") (pinfunction "D_5") (pintype "passive"))
      (node (ref "M1") (pin "6") (pinfunction "D_6") (pintype "passive"))
      (node (ref "M1") (pin "7") (pinfunction "D_7") (pintype "passive"))
      (node (ref "M1") (pin "8") (pinfunction "D_8") (pintype "passive"))
      (node (ref "M3") (pin "5") (pinfunction "D_5") (pintype "passive"))
      (node (ref "M3") (pin "6") (pinfunction "D_6") (pintype "passive"))
      (node (ref "M3") (pin "7") (pinfunction "D_7") (pintype "passive"))
      (node (ref "M3") (pin "8") (pinfunction "D_8") (pintype "passive"))
      (node (ref "R9") (pin "2") (pinfunction "2_2") (pintype "passive"))
      (node (ref "Ron1") (pin "2") (pinfunction "2_2") (pintype "passive"))
      (node (ref "U2") (pin "2") (pinfunction "VIN_2") (pintype "power_in"))
      (node (ref "U6") (pin "2") (pinfunction "VIN_2") (pintype "power_in"))
    )
    (net (code "30") (name "unconnected-(U2-EN-Pad3)") (class "Default")
      (node (ref "U2") (pin "3") (pinfunction "EN_3") (pintype "input+no_connect"))
    )
    (net (code "31") (name "unconnected-(U5-NC-Pad5)") (class "Default")
      (node (ref "U5") (pin "5") (pinfunction "NC_5") (pintype "passive+no_connect"))
    )
    (net (code "32") (name "unconnected-(U5-PG-Pad3)") (class "Default")
      (node (ref "U5") (pin "3") (pinfunction "PG_3") (pintype "open_collector+no_connect"))
    )
    (net (code "33") (name "unconnected-(U6-EN-Pad3)") (class "Default")
      (node (ref "U6") (pin "3") (pinfunction "EN_3") (pintype "input+no_connect"))
    )
  )
)
